# EVB-ANNA-B5_SCHEM_0001_Power.net
KiCad netlist of a schematic drawn in Altium Designer
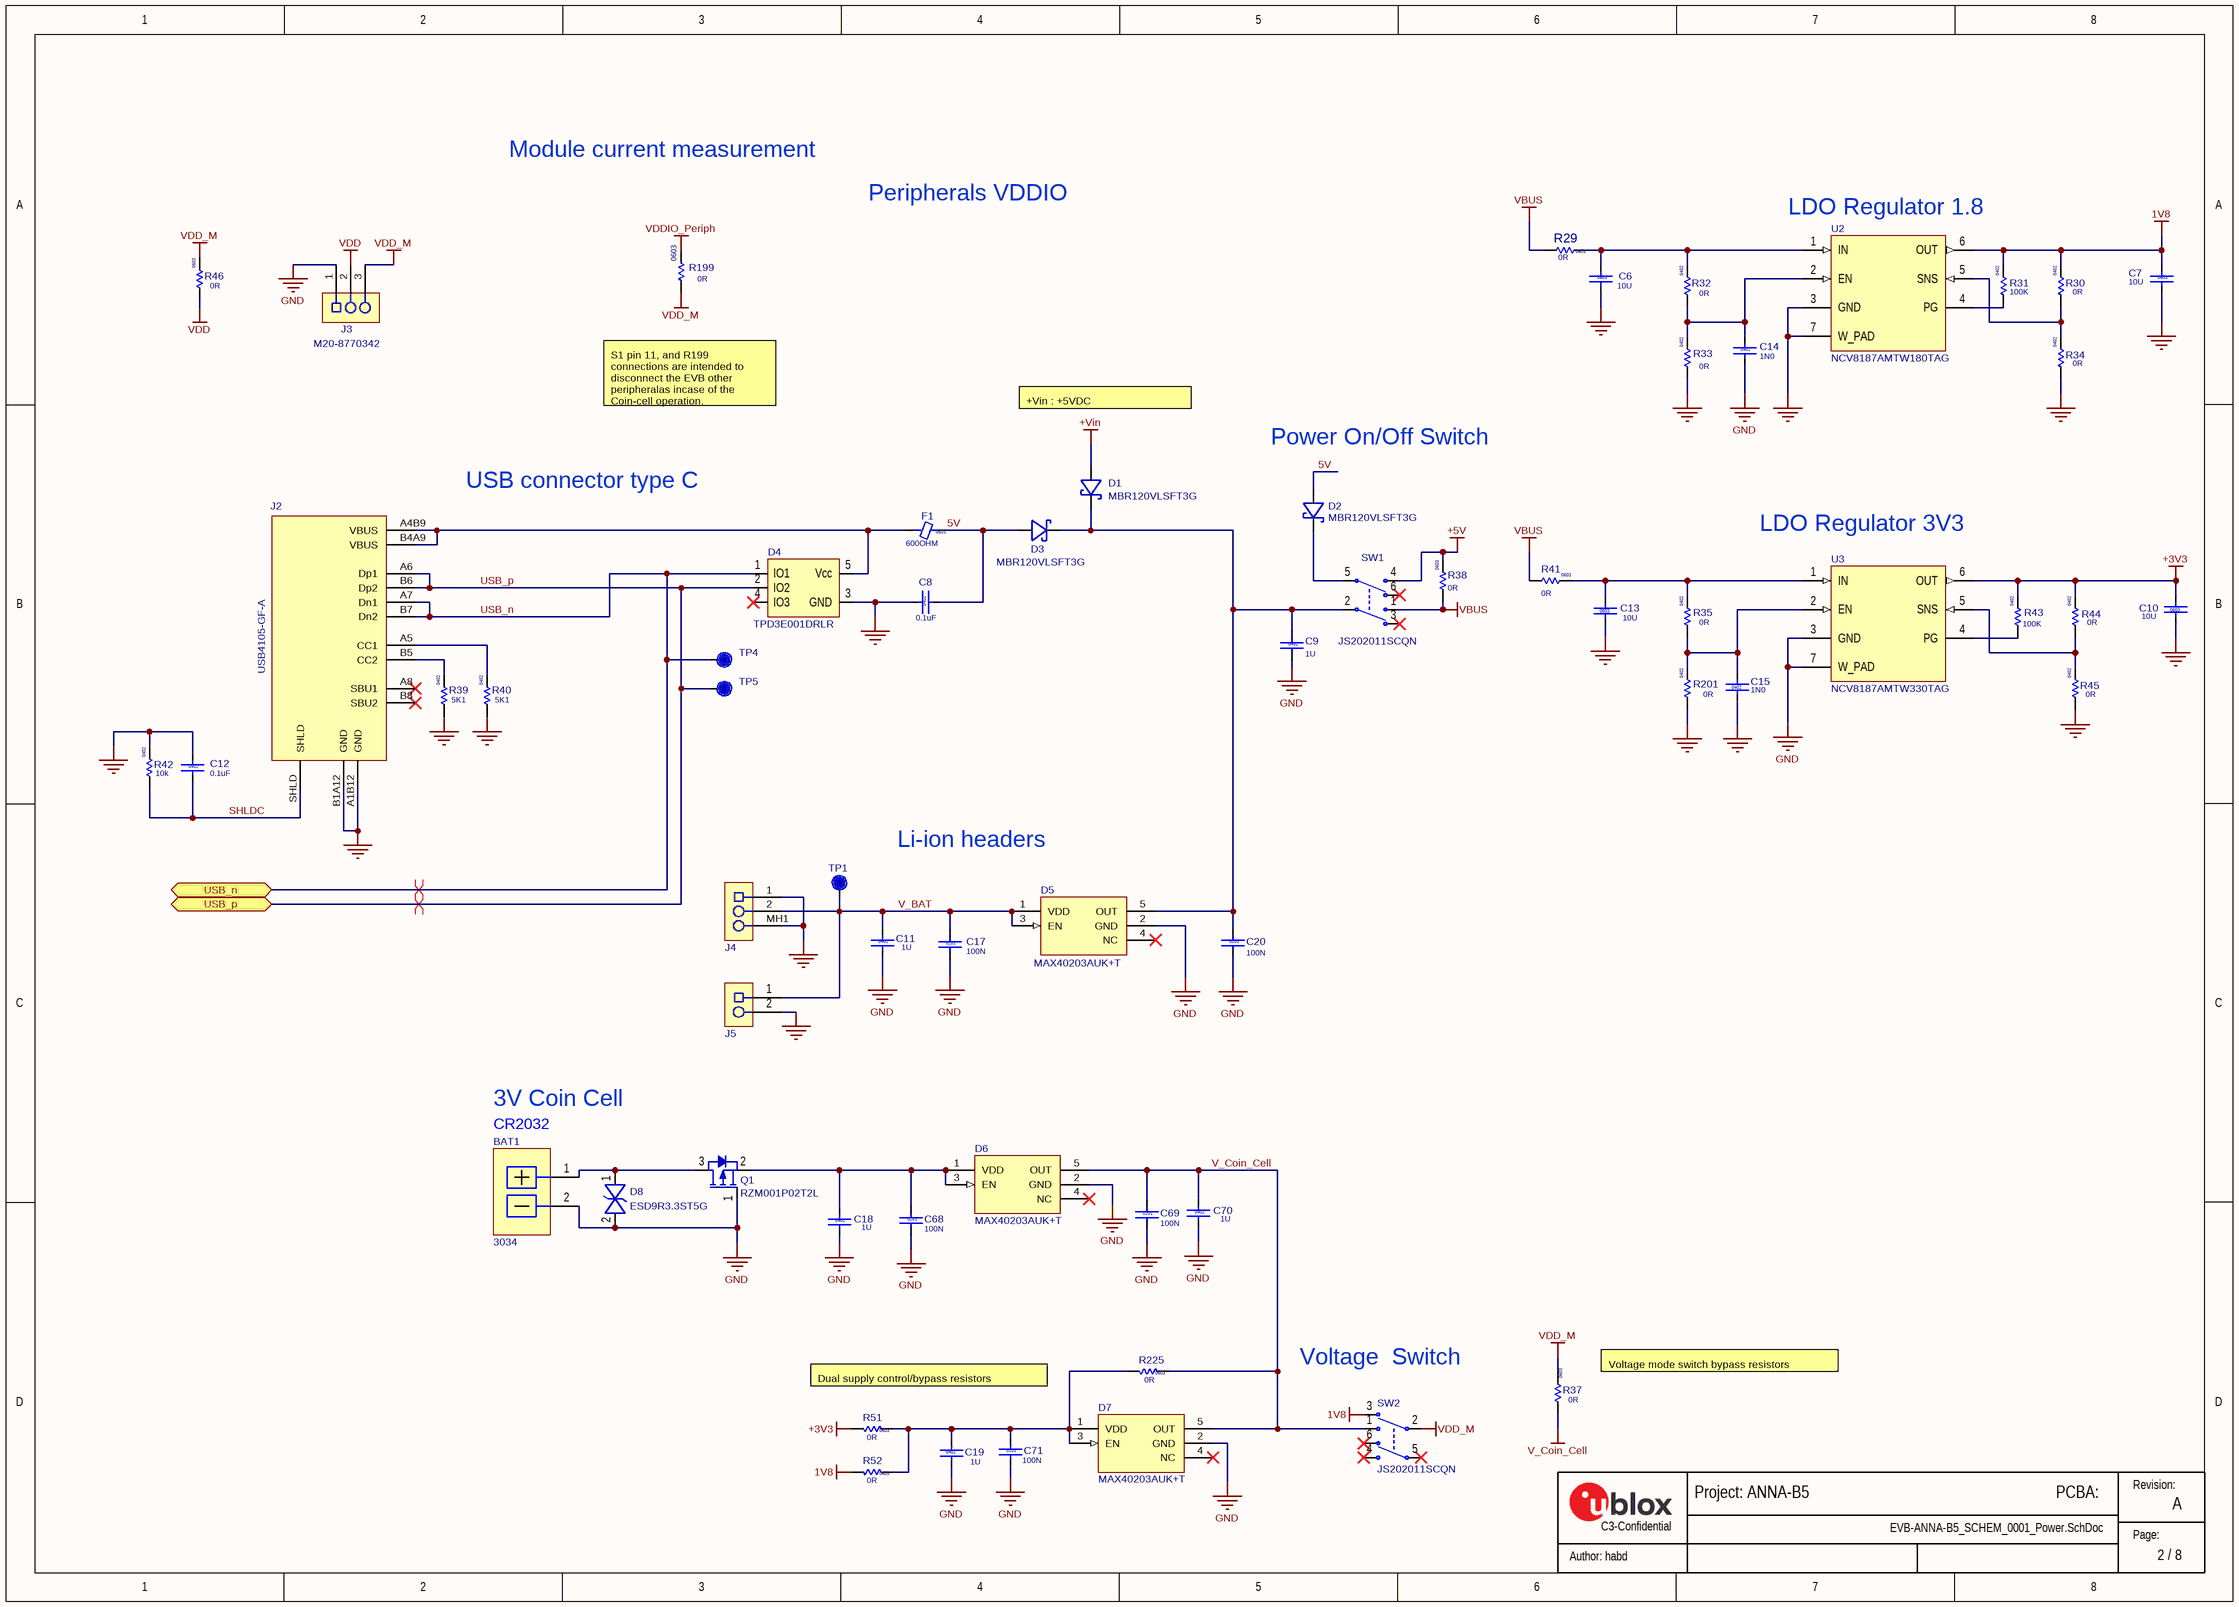
[diagram p0: EVB-ANNA-B5_SCHEM_0001_Power.SchDoc]

(export (version "E")
  (design (tool "Eeschema 10.0.6"))
  (components
    (comp (ref "BAT1")
      (value "UBXH03-0000009")
      (footprint "3034")
      (description "BATTERY HOLDER COIN SMT CR2020 CR2025 CR2032 KEYSTONE 3034")
      (fields
        (field (name "MANUFACTURER P/N") "3034")
        (field (name "MANUFACTURER") "Keystone Electronics Corporation")
        (field (name "EDITOR") "eric.moog")
      )
      (libsource (lib "UBX_Parts_DB_Lib") (part "Battery_2Pin"))
    )
    (comp (ref "C6")
      (value "10U")
      (footprint "CAP_0603_1750Lx950Wx850H_600x1000Pad_900G_FLX")
      (description "CAP CER X7R 0603 10U 20% 10V")
      (fields
        (field (name "SIZE") "0603")
        (field (name "PART NUMBER") "UBXH01-0000310")
        (field (name "TOLERANCE") "20%")
        (field (name "EDITOR") "michael.hein")
        (field (name "RELEASED BY") "martin.grasse")
      )
      (libsource (lib "UBX_Parts_DB_Lib") (part "Cap Chip"))
    )
    (comp (ref "C7")
      (value "10U")
      (footprint "CAP_0603_1750Lx950Wx850H_600x1000Pad_900G_FLX")
      (description "CAP CER X7R 0603 10U 20% 10V")
      (fields
        (field (name "SIZE") "0603")
        (field (name "PART NUMBER") "UBXH01-0000310")
        (field (name "TOLERANCE") "20%")
        (field (name "EDITOR") "michael.hein")
        (field (name "RELEASED BY") "martin.grasse")
      )
      (libsource (lib "UBX_Parts_DB_Lib") (part "Cap Chip"))
    )
    (comp (ref "C8")
      (value "0.1uF")
      (footprint "Cap 0402 HD")
      (description "Cap, Ceramic 0.1uF 10V 10% X5R 0402")
      (fields
        (field (name "SIZE") "0402")
        (field (name "PART NUMBER") "120-00016")
        (field (name "MANUFACTURER") "Murata Electronics North America")
      )
      (libsource (lib "Arena_Parts_DB_Lib") (part "Cap Chip"))
    )
    (comp (ref "C9")
      (value "1U")
      (footprint "Cap 0402 HD")
      (description "CAP CER X5R 0402 1U 10% 10V")
      (fields
        (field (name "SIZE") "0402")
        (field (name "PART NUMBER") "UBXH01-0000248")
        (field (name "TOLERANCE") "10%")
        (field (name "EDITOR") "michael.hein")
        (field (name "RELEASED BY") "igor.shevchenko")
      )
      (libsource (lib "UBX_Parts_DB_Lib") (part "Cap Chip"))
    )
    (comp (ref "C10")
      (value "10U")
      (footprint "CAP_0603_1750Lx950Wx850H_600x1000Pad_900G_FLX")
      (description "CAP CER X7R 0603 10U 20% 10V")
      (fields
        (field (name "SIZE") "0603")
        (field (name "PART NUMBER") "UBXH01-0000310")
        (field (name "TOLERANCE") "20%")
        (field (name "EDITOR") "michael.hein")
        (field (name "RELEASED BY") "martin.grasse")
      )
      (libsource (lib "UBX_Parts_DB_Lib") (part "Cap Chip"))
    )
    (comp (ref "C11")
      (value "1U")
      (footprint "Cap 0402 HD")
      (description "CAP CER X5R 0402 1U 10% 10V")
      (fields
        (field (name "SIZE") "0402")
        (field (name "PART NUMBER") "UBXH01-0000248")
        (field (name "TOLERANCE") "10%")
        (field (name "EDITOR") "michael.hein")
        (field (name "RELEASED BY") "igor.shevchenko")
      )
      (libsource (lib "UBX_Parts_DB_Lib") (part "Cap Chip"))
    )
    (comp (ref "C12")
      (value "0.1uF")
      (footprint "Cap 0402 HD")
      (description "Cap, Ceramic 0.1uF 10V 10% X5R 0402")
      (fields
        (field (name "SIZE") "0402")
        (field (name "PART NUMBER") "120-00016")
        (field (name "MANUFACTURER") "Murata Electronics North America")
      )
      (libsource (lib "Arena_Parts_DB_Lib") (part "Cap Chip"))
    )
    (comp (ref "C13")
      (value "10U")
      (footprint "CAP_0603_1750Lx950Wx850H_600x1000Pad_900G_FLX")
      (description "CAP CER X7R 0603 10U 20% 10V")
      (fields
        (field (name "SIZE") "0603")
        (field (name "PART NUMBER") "UBXH01-0000310")
        (field (name "TOLERANCE") "20%")
        (field (name "EDITOR") "michael.hein")
        (field (name "RELEASED BY") "martin.grasse")
      )
      (libsource (lib "UBX_Parts_DB_Lib") (part "Cap Chip"))
    )
    (comp (ref "C14")
      (value "1N0")
      (footprint "Cap 0402 HD")
      (description "CAP CER X7R 0402 1N0 10% 50V")
      (fields
        (field (name "SIZE") "0402")
        (field (name "PART NUMBER") "UBXH01-0000013")
        (field (name "TOLERANCE") "10%")
        (field (name "EDITOR") "massimo.vlacci")
        (field (name "RELEASED BY") "dario.antonaz")
      )
      (libsource (lib "UBX_Parts_DB_Lib") (part "Cap Chip"))
    )
    (comp (ref "C15")
      (value "1N0")
      (footprint "Cap 0402 HD")
      (description "CAP CER X7R 0402 1N0 10% 50V")
      (fields
        (field (name "SIZE") "0402")
        (field (name "PART NUMBER") "UBXH01-0000013")
        (field (name "TOLERANCE") "10%")
        (field (name "EDITOR") "massimo.vlacci")
        (field (name "RELEASED BY") "dario.antonaz")
      )
      (libsource (lib "UBX_Parts_DB_Lib") (part "Cap Chip"))
    )
    (comp (ref "C17")
      (value "100N")
      (footprint "Cap 0201 HD")
      (description "CAP CER X5R 0201 100N 10% 25V")
      (fields
        (field (name "CASE/PACKAGE") "0201")
        (field (name "TOLERANCE") "10%")
        (field (name "CRITICAL PART") "No")
        (field (name "OWNER") "Dario Antonaz (null)")
      )
      (libsource (lib "u-blox") (part "Cap Chip"))
    )
    (comp (ref "C18")
      (value "1U")
      (footprint "Cap 0402 HD")
      (description "CAP CER X5R 0402 1U 10% 10V")
      (fields
        (field (name "SIZE") "0402")
        (field (name "PART NUMBER") "UBXH01-0000248")
        (field (name "TOLERANCE") "10%")
        (field (name "EDITOR") "michael.hein")
        (field (name "RELEASED BY") "igor.shevchenko")
      )
      (libsource (lib "UBX_Parts_DB_Lib") (part "Cap Chip"))
    )
    (comp (ref "C19")
      (value "1U")
      (footprint "Cap 0402 HD")
      (description "CAP CER X5R 0402 1U 10% 10V")
      (fields
        (field (name "PART NUMBER") "UBXH01-0000248")
        (field (name "TOLERANCE") "10%")
        (field (name "SIZE") "0402")
        (field (name "EDITOR") "michael.hein")
        (field (name "RELEASED BY") "igor.shevchenko")
      )
      (libsource (lib "UBX_Parts_DB_Lib") (part "Cap Chip"))
    )
    (comp (ref "C20")
      (value "100N")
      (footprint "Cap 0201 HD")
      (description "CAP CER X5R 0201 100N 10% 25V")
      (fields
        (field (name "CASE/PACKAGE") "0201")
        (field (name "TOLERANCE") "10%")
        (field (name "CRITICAL PART") "No")
        (field (name "OWNER") "Dario Antonaz (null)")
      )
      (libsource (lib "u-blox") (part "Cap Chip"))
    )
    (comp (ref "C68")
      (value "100N")
      (footprint "Cap 0201 HD")
      (description "CAP CER X5R 0201 100N 10% 25V")
      (fields
        (field (name "CASE/PACKAGE") "0201")
        (field (name "TOLERANCE") "10%")
        (field (name "CRITICAL PART") "No")
        (field (name "OWNER") "Dario Antonaz (null)")
      )
      (libsource (lib "u-blox") (part "Cap Chip"))
    )
    (comp (ref "C69")
      (value "100N")
      (footprint "Cap 0201 HD")
      (description "CAP CER X5R 0201 100N 10% 25V")
      (fields
        (field (name "CASE/PACKAGE") "0201")
        (field (name "TOLERANCE") "10%")
        (field (name "CRITICAL PART") "No")
        (field (name "OWNER") "Dario Antonaz (null)")
      )
      (libsource (lib "u-blox") (part "Cap Chip"))
    )
    (comp (ref "C70")
      (value "1U")
      (footprint "Cap 0402 HD")
      (description "CAP CER X5R 0402 1U 10% 10V")
      (fields
        (field (name "SIZE") "0402")
        (field (name "PART NUMBER") "UBXH01-0000248")
        (field (name "TOLERANCE") "10%")
        (field (name "EDITOR") "michael.hein")
        (field (name "RELEASED BY") "igor.shevchenko")
      )
      (libsource (lib "UBX_Parts_DB_Lib") (part "Cap Chip"))
    )
    (comp (ref "C71")
      (value "100N")
      (footprint "Cap 0201 HD")
      (description "CAP CER X5R 0201 100N 10% 25V")
      (fields
        (field (name "CASE/PACKAGE") "0201")
        (field (name "TOLERANCE") "10%")
        (field (name "CRITICAL PART") "No")
        (field (name "OWNER") "Dario Antonaz (null)")
      )
      (libsource (lib "u-blox") (part "Cap Chip"))
    )
    (comp (ref "D1")
      (value "110-00005")
      (footprint "SOD-123F_U")
      (description "Diode, Schottky, 20V 1A SOD-123F, 340mV Vf @ 1A\nMBR120VLSFT3G")
      (fields (field (name "MANUFACTURER PART NUMBER 1") "MBR120VLSFT3G") (field (name "VOLTAGE") "20V"))
      (libsource (lib "Arena_Parts_DB_Lib") (part "Diode_Schottky"))
    )
    (comp (ref "D2")
      (value "110-00005")
      (footprint "SOD-123F_U")
      (description "Diode, Schottky, 20V 1A SOD-123F, 340mV Vf @ 1A\nMBR120VLSFT3G")
      (fields (field (name "MANUFACTURER PART NUMBER 1") "MBR120VLSFT3G") (field (name "VOLTAGE") "20V"))
      (libsource (lib "Arena_Parts_DB_Lib") (part "Diode_Schottky"))
    )
    (comp (ref "D3")
      (value "110-00005")
      (footprint "SOD-123F_U")
      (description "Diode, Schottky, 20V 1A SOD-123F, 340mV Vf @ 1A\nMBR120VLSFT3G")
      (fields (field (name "MANUFACTURER PART NUMBER 1") "MBR120VLSFT3G") (field (name "VOLTAGE") "20V"))
      (libsource (lib "Arena_Parts_DB_Lib") (part "Diode_Schottky"))
    )
    (comp (ref "D4")
      (value "110-00018")
      (footprint "SOT-553")
      (description "LOW-CAPACITANCE 3-CHANNEL ESD-PROTECTION ARRAY")
      (fields
        (field (name "MANUFACTURER P/N") "TPD3E001DRLR")
        (field (name "MANUFACTURER") "Texas Instruments")
        (field (name "VOLTAGE") "5V")
      )
      (libsource (lib "Arena_Parts_DB_Lib") (part "TPD3E001"))
    )
    (comp (ref "D5")
      (value "UBXH12-0000539")
      (footprint "SOT-23-5_2")
      (description "IDEAL DIODE OR CONTROLLER SOURCE SELECTOR SWITCH P-CHANNEL 1:1 SOT-23-5 5.5V 1A")
      (fields
        (field (name "VOLTAGE") "5.5V")
        (field (name "MANUFACTURER PART NUMBER 1") "MAX40203AUK+T")
        (field (name "MANUFACTURER") "Maxim")
        (field (name "EDITOR") "eric.moog")
      )
      (libsource (lib "UBX_Parts_DB_Lib") (part "MAX40203AUK"))
    )
    (comp (ref "D6")
      (value "UBXH12-0000539")
      (footprint "SOT-23-5_2")
      (description "IDEAL DIODE OR CONTROLLER SOURCE SELECTOR SWITCH P-CHANNEL 1:1 SOT-23-5 5.5V 1A")
      (fields
        (field (name "VOLTAGE") "5.5V")
        (field (name "MANUFACTURER PART NUMBER 1") "MAX40203AUK+T")
        (field (name "MANUFACTURER") "Maxim")
        (field (name "EDITOR") "eric.moog")
      )
      (libsource (lib "UBX_Parts_DB_Lib") (part "MAX40203AUK"))
    )
    (comp (ref "D7")
      (value "UBXH12-0000539")
      (footprint "SOT-23-5_2")
      (description "IDEAL DIODE OR CONTROLLER SOURCE SELECTOR SWITCH P-CHANNEL 1:1 SOT-23-5 5.5V 1A")
      (fields
        (field (name "VOLTAGE") "5.5V")
        (field (name "MANUFACTURER PART NUMBER 1") "MAX40203AUK+T")
        (field (name "MANUFACTURER") "Maxim")
        (field (name "EDITOR") "eric.moog")
      )
      (libsource (lib "UBX_Parts_DB_Lib") (part "MAX40203AUK"))
    )
    (comp (ref "D8")
      (value "UBXH07-0000034")
      (footprint "SOD-923")
      (description "ESD PROTECTION DIODE ULTRA LOW LEAKAGE SOD923 ON SEMI 3V3")
      (fields
        (field (name "MANUFACTURER") "ON Semiconductor")
        (field (name "MANUFACTURER P/N") "ESD9R3.3ST5G")
        (field (name "EDITOR") "pierpaolo.arban")
        (field (name "RELEASED BY") "dario.antonaz")
      )
      (libsource (lib "UBX_Parts_DB_Lib") (part "Diode_TVS"))
    )
    (comp (ref "F1")
      (value "600OHM")
      (footprint "IND_0603_1750Lx950Wx1050H_600x800Pad_800G_FLX")
      (description "FERRITE BEAD 0603 600 OHM AT 100MHZ 600OHM 500mA")
      (fields
        (field (name "SIZE") "0603")
        (field (name "PART NUMBER") "UBXH08-0000001")
        (field (name "MANUFACTURER") "TDK Corporation")
        (field (name "EDITOR") "daniel.hurni")
        (field (name "RELEASED BY") "martin.frauchiger")
      )
      (libsource (lib "UBX_Parts_DB_Lib") (part "FB sm"))
    )
    (comp (ref "J2")
      (value "USB4105-GF-A")
      (footprint "USB4105-GF-A")
      (description "CONN RCP USB2.0 TYP C 24P SMD RA 20V 6.25A")
      (fields
        (field (name "PART NUMBER") "UBXH04-0000785")
        (field (name "VOLTAGE") "<20V DC")
        (field (name "EDITOR") "eric.moog")
      )
      (libsource (lib "UBX_Parts_DB_Lib") (part "USB4105-GF-A"))
    )
    (comp (ref "J3")
      (value "UBXH04-0000792")
      (footprint "HDR-0.1P-3Pin-1Row-SMT")
      (description "1-ROW SMD CONN 100MIL GRID 3 -PIN 100V 3A")
      (fields
        (field (name "MANUFACTURER P/N") "M20-8770342")
        (field (name "MANUFACTURER") "HARWiN")
        (field (name "EDITOR") "eric.moog")
      )
      (libsource (lib "UBX_Parts_DB_Lib") (part "CON-3Pin_1Row"))
    )
    (comp (ref "J4")
      (value "UBXH04-0000791")
      (footprint "B2B-PH-SM4-TB")
      (description "CONN 1-ROW SMT 2.0MM GRID 2-PIN VERT 100V 2A")
      (fields
        (field (name "VOLTAGE") "None")
        (field (name "MANUFACTURER") "JST")
        (field (name "EDITOR") "eric.moog")
      )
      (libsource (lib "UBX_Parts_DB_Lib") (part "CON-2Pin_1Row_W-MH"))
    )
    (comp (ref "J5")
      (value "UBXH04-0000026")
      (footprint "HDR-0.1P-2PIN-TH")
      (description "1-ROW TH-PCB SOCKETS 100MIL GRID 2-PIN 0.64MM SQUARE POLARIZE")
      (fields
        (field (name "MANUFACTURER") "HARWiN")
        (field (name "EDITOR") "roland.rust")
        (field (name "RELEASED BY") "alvaro.nussbaum")
      )
      (libsource (lib "UBX_Parts_DB_Lib") (part "CON-2Pin_1Row"))
    )
    (comp (ref "Q1")
      (value "140-00005")
      (footprint "SOT-723")
      (description "P-MOSFET, 20V, 100mA, SOT-723-3")
      (fields (field (name "VOLTAGE") "20V") (field (name "MANUFACTURER PART NUMBER 1") "RZM001P02T2L"))
      (libsource (lib "Arena_Parts_DB_Lib") (part "MOSFET-P"))
    )
    (comp (ref "R29")
      (value "0R")
      (footprint "RES_0603_1700Lx950Wx600H_600x1000Pad_800G_FLX")
      (description "RES THICK FILM CHIP 0603 0R 0 100mW")
      (fields
        (field (name "SIZE") "0603")
        (field (name "PART NUMBER") "UBXH18-0003001")
        (field (name "TOLERANCE") "0")
        (field (name "EDITOR") "martin.frauchiger")
        (field (name "RELEASED BY") "martin.frauchiger")
      )
      (libsource (lib "UBX_Parts_DB_Lib") (part "Res sm"))
    )
    (comp (ref "R30")
      (value "0R")
      (footprint "RES 0402 HD")
      (description "RES THICK FILM CHIP 0402 0R 0 100mW")
      (fields
        (field (name "SIZE") "0402")
        (field (name "PART NUMBER") "UBXH18-0003002")
        (field (name "TOLERANCE") "0")
        (field (name "EDITOR") "charlotte.biber")
        (field (name "RELEASED BY") "peter.mueller")
      )
      (libsource (lib "UBX_Parts_DB_Lib") (part "Res sm"))
    )
    (comp (ref "R31")
      (value "100K")
      (footprint "RES 0402 HD")
      (description "RES THICK FILM CHIP 0402 100K 1% 63mW")
      (fields
        (field (name "SIZE") "0402")
        (field (name "PART NUMBER") "UBXH18-0000005")
        (field (name "TOLERANCE") "1%")
        (field (name "EDITOR") "dario.antonaz")
        (field (name "RELEASED BY") "sandro.sestan")
      )
      (libsource (lib "UBX_Parts_DB_Lib") (part "Res sm"))
    )
    (comp (ref "R32")
      (value "0R")
      (footprint "RES 0402 HD")
      (description "RES THICK FILM CHIP 0402 0R 0 100mW")
      (fields
        (field (name "SIZE") "0402")
        (field (name "PART NUMBER") "UBXH18-0003002")
        (field (name "TOLERANCE") "0")
        (field (name "EDITOR") "charlotte.biber")
        (field (name "RELEASED BY") "peter.mueller")
      )
      (libsource (lib "UBX_Parts_DB_Lib") (part "Res sm"))
    )
    (comp (ref "R33")
      (value "0R")
      (footprint "RES 0402 HD")
      (description "RES THICK FILM CHIP 0402 0R 0 100mW")
      (fields
        (field (name "SIZE") "0402")
        (field (name "PART NUMBER") "UBXH18-0003002")
        (field (name "TOLERANCE") "0")
        (field (name "EDITOR") "charlotte.biber")
        (field (name "RELEASED BY") "peter.mueller")
      )
      (libsource (lib "UBX_Parts_DB_Lib") (part "Res sm"))
    )
    (comp (ref "R34")
      (value "0R")
      (footprint "RES 0402 HD")
      (description "RES THICK FILM CHIP 0402 0R 0 100mW")
      (fields
        (field (name "SIZE") "0402")
        (field (name "PART NUMBER") "UBXH18-0003002")
        (field (name "TOLERANCE") "0")
        (field (name "EDITOR") "charlotte.biber")
        (field (name "RELEASED BY") "peter.mueller")
      )
      (libsource (lib "UBX_Parts_DB_Lib") (part "Res sm"))
    )
    (comp (ref "R35")
      (value "0R")
      (footprint "RES 0402 HD")
      (description "RES THICK FILM CHIP 0402 0R 0 100mW")
      (fields
        (field (name "SIZE") "0402")
        (field (name "PART NUMBER") "UBXH18-0003002")
        (field (name "TOLERANCE") "0")
        (field (name "EDITOR") "charlotte.biber")
        (field (name "RELEASED BY") "peter.mueller")
      )
      (libsource (lib "UBX_Parts_DB_Lib") (part "Res sm"))
    )
    (comp (ref "R37")
      (value "0R")
      (footprint "RES_0603_1700Lx950Wx600H_600x1000Pad_800G_FLX")
      (description "RES THICK FILM CHIP 0603 0R 0 100mW")
      (fields
        (field (name "SIZE") "0603")
        (field (name "PART NUMBER") "UBXH18-0003001")
        (field (name "TOLERANCE") "0")
        (field (name "EDITOR") "martin.frauchiger")
        (field (name "RELEASED BY") "martin.frauchiger")
      )
      (libsource (lib "UBX_Parts_DB_Lib") (part "Res sm"))
    )
    (comp (ref "R38")
      (value "0R")
      (footprint "RES_0603_1700Lx950Wx600H_600x1000Pad_800G_FLX")
      (description "RES THICK FILM CHIP 0603 0R 0 100mW")
      (fields
        (field (name "SIZE") "0603")
        (field (name "PART NUMBER") "UBXH18-0003001")
        (field (name "TOLERANCE") "0")
        (field (name "EDITOR") "martin.frauchiger")
        (field (name "RELEASED BY") "martin.frauchiger")
      )
      (libsource (lib "UBX_Parts_DB_Lib") (part "Res sm"))
    )
    (comp (ref "R39")
      (value "5K1")
      (footprint "RES 0402 HD")
      (description "RES THICK FILM CHIP 0402 5K1 5% 100mW")
      (fields
        (field (name "SIZE") "0402")
        (field (name "PART NUMBER") "UBXH18-0008066")
        (field (name "TOLERANCE") "5%")
        (field (name "EDITOR") "alvaro.nussbaum")
        (field (name "RELEASED BY") "roland.rust")
      )
      (libsource (lib "UBX_Parts_DB_Lib") (part "Res sm"))
    )
    (comp (ref "R40")
      (value "5K1")
      (footprint "RES 0402 HD")
      (description "RES THICK FILM CHIP 0402 5K1 5% 100mW")
      (fields
        (field (name "SIZE") "0402")
        (field (name "PART NUMBER") "UBXH18-0008066")
        (field (name "TOLERANCE") "5%")
        (field (name "EDITOR") "alvaro.nussbaum")
        (field (name "RELEASED BY") "roland.rust")
      )
      (libsource (lib "UBX_Parts_DB_Lib") (part "Res sm"))
    )
    (comp (ref "R41")
      (value "0R")
      (footprint "RES_0603_1700Lx950Wx600H_600x1000Pad_800G_FLX")
      (description "RES THICK FILM CHIP 0603 0R 0 100mW")
      (fields
        (field (name "SIZE") "0603")
        (field (name "PART NUMBER") "UBXH18-0003001")
        (field (name "TOLERANCE") "0")
        (field (name "EDITOR") "martin.frauchiger")
        (field (name "RELEASED BY") "martin.frauchiger")
      )
      (libsource (lib "UBX_Parts_DB_Lib") (part "Res sm"))
    )
    (comp (ref "R42")
      (value "10k")
      (footprint "RES 0402 HD")
      (description "Resistor 10k ohm 1% 1/16W, 0402")
      (fields
        (field (name "SIZE") "0402")
        (field (name "PART NUMBER") "180-00024")
        (field (name "POWER") "1/16W")
      )
      (libsource (lib "Arena_Parts_DB_Lib") (part "Res sm"))
    )
    (comp (ref "R43")
      (value "100K")
      (footprint "RES 0402 HD")
      (description "RES THICK FILM CHIP 0402 100K 1% 63mW")
      (fields
        (field (name "SIZE") "0402")
        (field (name "PART NUMBER") "UBXH18-0000005")
        (field (name "TOLERANCE") "1%")
        (field (name "EDITOR") "dario.antonaz")
        (field (name "RELEASED BY") "sandro.sestan")
      )
      (libsource (lib "UBX_Parts_DB_Lib") (part "Res sm"))
    )
    (comp (ref "R44")
      (value "0R")
      (footprint "RES 0402 HD")
      (description "RES THICK FILM CHIP 0402 0R 0 100mW")
      (fields
        (field (name "SIZE") "0402")
        (field (name "PART NUMBER") "UBXH18-0003002")
        (field (name "TOLERANCE") "0")
        (field (name "EDITOR") "charlotte.biber")
        (field (name "RELEASED BY") "peter.mueller")
      )
      (libsource (lib "UBX_Parts_DB_Lib") (part "Res sm"))
    )
    (comp (ref "R45")
      (value "0R")
      (footprint "RES 0402 HD")
      (description "RES THICK FILM CHIP 0402 0R 0 100mW")
      (fields
        (field (name "SIZE") "0402")
        (field (name "PART NUMBER") "UBXH18-0003002")
        (field (name "TOLERANCE") "0")
        (field (name "EDITOR") "charlotte.biber")
        (field (name "RELEASED BY") "peter.mueller")
      )
      (libsource (lib "UBX_Parts_DB_Lib") (part "Res sm"))
    )
    (comp (ref "R46")
      (value "0R")
      (footprint "RES_0603_1700Lx950Wx600H_600x1000Pad_800G_FLX")
      (description "RES THICK FILM CHIP 0603 0R 0 100mW")
      (fields
        (field (name "SIZE") "0603")
        (field (name "PART NUMBER") "UBXH18-0003001")
        (field (name "TOLERANCE") "0")
        (field (name "EDITOR") "martin.frauchiger")
        (field (name "RELEASED BY") "martin.frauchiger")
      )
      (libsource (lib "UBX_Parts_DB_Lib") (part "Res sm"))
    )
    (comp (ref "R51")
      (value "0R")
      (footprint "RES_0603_1700Lx950Wx600H_600x1000Pad_800G_FLX")
      (description "RES THICK FILM CHIP 0603 0R 0 100mW")
      (fields
        (field (name "SIZE") "0603")
        (field (name "PART NUMBER") "UBXH18-0003001")
        (field (name "TOLERANCE") "0")
        (field (name "EDITOR") "martin.frauchiger")
        (field (name "RELEASED BY") "martin.frauchiger")
      )
      (libsource (lib "UBX_Parts_DB_Lib") (part "Res sm"))
    )
    (comp (ref "R52")
      (value "0R")
      (footprint "RES_0603_1700Lx950Wx600H_600x1000Pad_800G_FLX")
      (description "RES THICK FILM CHIP 0603 0R 0 100mW")
      (fields
        (field (name "SIZE") "0603")
        (field (name "PART NUMBER") "UBXH18-0003001")
        (field (name "TOLERANCE") "0")
        (field (name "EDITOR") "martin.frauchiger")
        (field (name "RELEASED BY") "martin.frauchiger")
      )
      (libsource (lib "UBX_Parts_DB_Lib") (part "Res sm"))
    )
    (comp (ref "R199")
      (value "0R")
      (footprint "RES_0603_1700Lx950Wx600H_600x1000Pad_800G_FLX")
      (description "RES THICK FILM CHIP 0603 0R 0 100mW")
      (fields
        (field (name "SIZE") "0603")
        (field (name "PART NUMBER") "UBXH18-0003001")
        (field (name "TOLERANCE") "0")
        (field (name "EDITOR") "martin.frauchiger")
        (field (name "RELEASED BY") "martin.frauchiger")
      )
      (libsource (lib "UBX_Parts_DB_Lib") (part "Res sm"))
    )
    (comp (ref "R201")
      (value "0R")
      (footprint "RES 0402 HD")
      (description "RES THICK FILM CHIP 0402 0R 0 100mW")
      (fields
        (field (name "SIZE") "0402")
        (field (name "PART NUMBER") "UBXH18-0003002")
        (field (name "TOLERANCE") "0")
        (field (name "EDITOR") "charlotte.biber")
        (field (name "RELEASED BY") "peter.mueller")
      )
      (libsource (lib "UBX_Parts_DB_Lib") (part "Res sm"))
    )
    (comp (ref "R225")
      (value "0R")
      (footprint "RES_0603_1700Lx950Wx600H_600x1000Pad_800G_FLX")
      (description "RES THICK FILM CHIP 0603 0R 0 100mW")
      (fields
        (field (name "SIZE") "0603")
        (field (name "PART NUMBER") "UBXH18-0003001")
        (field (name "TOLERANCE") "0")
        (field (name "EDITOR") "martin.frauchiger")
        (field (name "RELEASED BY") "martin.frauchiger")
      )
      (libsource (lib "UBX_Parts_DB_Lib") (part "Res sm"))
    )
    (comp (ref "SW1")
      (value "UBXH19-0000050")
      (footprint "SW_Slide_DPDT_JS202011SCQN")
      (description "2 WAY ON-ON SUB-MINIATURE SLIDE SWITCH SMD JS SERIES")
      (fields
        (field (name "MANUFACTURER P/N") "JS202011SCQN")
        (field (name "MANUFACTURER") "C&K Components")
        (field (name "EDITOR") "andre.pick")
        (field (name "RELEASED BY") "martin.pilik")
      )
      (libsource (lib "UBX_Parts_DB_Lib") (part "SW_DPDT_JS2020"))
    )
    (comp (ref "SW2")
      (value "UBXH19-0000050")
      (footprint "SW_Slide_DPDT_JS202011SCQN")
      (description "2 WAY ON-ON SUB-MINIATURE SLIDE SWITCH SMD JS SERIES")
      (fields
        (field (name "MANUFACTURER P/N") "JS202011SCQN")
        (field (name "MANUFACTURER") "C&K Components")
        (field (name "EDITOR") "andre.pick")
        (field (name "RELEASED BY") "martin.pilik")
      )
      (libsource (lib "UBX_Parts_DB_Lib") (part "SW_DPDT_JS2020"))
    )
    (comp (ref "TP1")
      (value "TP10R")
      (footprint "TP10R")
      (description "Testpoint, Round 1.0mm Dia")
      (fields (field (name "ADDED BY") "Jeremy D") (field (name "CHECKED BY") "Paul B"))
      (libsource (lib "LEGACY_Rigado_AltiumLib") (part "TP_R"))
    )
    (comp (ref "TP4")
      (value "TP10R")
      (footprint "TP10R")
      (description "Testpoint, Round 1.0mm Dia")
      (fields (field (name "ADDED BY") "Jeremy D") (field (name "CHECKED BY") "Paul B"))
      (libsource (lib "") (part "TP_R_1"))
    )
    (comp (ref "TP5")
      (value "TP10R")
      (footprint "TP10R")
      (description "Testpoint, Round 1.0mm Dia")
      (fields (field (name "ADDED BY") "Jeremy D") (field (name "CHECKED BY") "Paul B"))
      (libsource (lib "") (part "TP_R_1"))
    )
    (comp (ref "U2")
      (value "UBXH43-0000004")
      (footprint "DFN0.65P-6Pin_W-Pad")
      (description "LDO REGULATOR 1.8V,LOW Iq, WDFNW6 2x2 MM PACKAGE 1200 mA")
      (fields
        (field (name "MANUFACTURER PART NUMBER 1") "NCV8187AMTW180TAG")
        (field (name "OWNER") "Hozaifa Abdelgadir")
      )
      (libsource (lib "UBX_Arena") (part "NCV8187"))
    )
    (comp (ref "U3")
      (value "UBXH43-0000003")
      (footprint "DFN0.65P-6Pin_W-Pad")
      (description "LDO REGULATOR 3.3V,LOW Iq, WDFNW6 2x2 MM, 0.65P PACKAGE 1200 mA")
      (fields
        (field (name "MANUFACTURER PART NUMBER 1") "NCV8187AMTW330TAG")
        (field (name "OWNER") "Hozaifa Abdelgadir")
      )
      (libsource (lib "UBX_Arena") (part "NCV8187"))
    )
  )
  (nets
    (net (code "1") (name "+3V3") (class "Default")
      (node (ref "C10") (pin "1") (pinfunction "1_1") (pintype "passive"))
      (node (ref "R43") (pin "2") (pinfunction "2_2") (pintype "passive"))
      (node (ref "R44") (pin "2") (pinfunction "2_2") (pintype "passive"))
      (node (ref "R51") (pin "2") (pinfunction "2_2") (pintype "passive"))
      (node (ref "U3") (pin "6") (pinfunction "OUT_6") (pintype "output"))
    )
    (net (code "2") (name "+5V") (class "Default")
      (node (ref "R38") (pin "2") (pinfunction "2_2") (pintype "passive"))
      (node (ref "SW1") (pin "4") (pinfunction "N.O-2_4") (pintype "passive"))
    )
    (net (code "3") (name "+Vin") (class "Default")
      (node (ref "D1") (pin "A") (pinfunction "Anode_A") (pintype "passive"))
    )
    (net (code "4") (name "/5V") (class "Default")
      (node (ref "C8") (pin "2") (pinfunction "2_2") (pintype "passive"))
      (node (ref "D2") (pin "A") (pinfunction "Anode_A") (pintype "passive"))
      (node (ref "D3") (pin "A") (pinfunction "Anode_A") (pintype "passive"))
      (node (ref "F1") (pin "2") (pinfunction "2_2") (pintype "passive"))
    )
    (net (code "5") (name "/SHLDC") (class "Default")
      (node (ref "C12") (pin "2") (pinfunction "2_2") (pintype "passive"))
      (node (ref "J2") (pin "SHLD") (pinfunction "SHLD_SHLD") (pintype "power_in"))
      (node (ref "R42") (pin "1") (pinfunction "1_1") (pintype "passive"))
    )
    (net (code "6") (name "/USB_n") (class "Default")
      (node (ref "D4") (pin "1") (pinfunction "IO1_1") (pintype "passive"))
      (node (ref "J2") (pin "A7") (pinfunction "Dn1_A7") (pintype "power_in"))
      (node (ref "J2") (pin "B7") (pinfunction "Dn2_B7") (pintype "power_in"))
      (node (ref "TP4") (pin "1") (pintype "passive"))
    )
    (net (code "7") (name "/USB_p") (class "Default")
      (node (ref "D4") (pin "2") (pinfunction "IO2_2") (pintype "passive"))
      (node (ref "J2") (pin "A6") (pinfunction "Dp1_A6") (pintype "power_in"))
      (node (ref "J2") (pin "B6") (pinfunction "Dp2_B6") (pintype "power_in"))
      (node (ref "TP5") (pin "1") (pintype "passive"))
    )
    (net (code "8") (name "/V_BAT") (class "Default")
      (node (ref "C11") (pin "1") (pinfunction "1_1") (pintype "passive"))
      (node (ref "C17") (pin "1") (pinfunction "1_1") (pintype "passive"))
      (node (ref "D5") (pin "1") (pinfunction "VDD_1") (pintype "power_in"))
      (node (ref "D5") (pin "3") (pinfunction "EN_3") (pintype "input"))
      (node (ref "J4") (pin "2") (pinfunction "2_2") (pintype "passive"))
      (node (ref "J5") (pin "1") (pinfunction "1_1") (pintype "passive"))
      (node (ref "TP1") (pin "1") (pintype "passive"))
    )
    (net (code "9") (name "1V8") (class "Default")
      (node (ref "C7") (pin "1") (pinfunction "1_1") (pintype "passive"))
      (node (ref "R30") (pin "2") (pinfunction "2_2") (pintype "passive"))
      (node (ref "R31") (pin "2") (pinfunction "2_2") (pintype "passive"))
      (node (ref "R52") (pin "2") (pinfunction "2_2") (pintype "passive"))
      (node (ref "SW2") (pin "3") (pinfunction "N.C-1_3") (pintype "passive"))
      (node (ref "U2") (pin "6") (pinfunction "OUT_6") (pintype "output"))
    )
    (net (code "10") (name "GND") (class "Default")
      (node (ref "BAT1") (pin "2") (pinfunction "2_2") (pintype "power_in"))
      (node (ref "C10") (pin "2") (pinfunction "2_2") (pintype "passive"))
      (node (ref "C11") (pin "2") (pinfunction "2_2") (pintype "passive"))
      (node (ref "C12") (pin "1") (pinfunction "1_1") (pintype "passive"))
      (node (ref "C13") (pin "2") (pinfunction "2_2") (pintype "passive"))
      (node (ref "C14") (pin "2") (pinfunction "2_2") (pintype "passive"))
      (node (ref "C15") (pin "1") (pinfunction "1_1") (pintype "passive"))
      (node (ref "C17") (pin "2") (pinfunction "2_2") (pintype "passive"))
      (node (ref "C18") (pin "2") (pinfunction "2_2") (pintype "passive"))
      (node (ref "C19") (pin "2") (pinfunction "2_2") (pintype "passive"))
      (node (ref "C20") (pin "2") (pinfunction "2_2") (pintype "passive"))
      (node (ref "C6") (pin "2") (pinfunction "2_2") (pintype "passive"))
      (node (ref "C68") (pin "2") (pinfunction "2_2") (pintype "passive"))
      (node (ref "C69") (pin "2") (pinfunction "2_2") (pintype "passive"))
      (node (ref "C7") (pin "2") (pinfunction "2_2") (pintype "passive"))
      (node (ref "C70") (pin "2") (pinfunction "2_2") (pintype "passive"))
      (node (ref "C71") (pin "2") (pinfunction "2_2") (pintype "passive"))
      (node (ref "C8") (pin "1") (pinfunction "1_1") (pintype "passive"))
      (node (ref "C9") (pin "2") (pinfunction "2_2") (pintype "passive"))
      (node (ref "D4") (pin "3") (pinfunction "GND_3") (pintype "power_in"))
      (node (ref "D5") (pin "2") (pinfunction "GND_2") (pintype "power_in"))
      (node (ref "D6") (pin "2") (pinfunction "GND_2") (pintype "power_in"))
      (node (ref "D7") (pin "2") (pinfunction "GND_2") (pintype "power_in"))
      (node (ref "D8") (pin "2") (pintype "passive"))
      (node (ref "J2") (pin "A1B12") (pinfunction "GND_A1B12") (pintype "power_in"))
      (node (ref "J2") (pin "B1A12") (pinfunction "GND_B1A12") (pintype "power_in"))
      (node (ref "J3") (pin "1") (pinfunction "1_1") (pintype "passive"))
      (node (ref "J4") (pin "1") (pinfunction "1_1") (pintype "passive"))
      (node (ref "J4") (pin "MH1") (pinfunction "MH1_MH1") (pintype "passive"))
      (node (ref "J5") (pin "2") (pinfunction "2_2") (pintype "passive"))
      (node (ref "Q1") (pin "1") (pinfunction "G_1") (pintype "passive"))
      (node (ref "R201") (pin "1") (pinfunction "1_1") (pintype "passive"))
      (node (ref "R33") (pin "1") (pinfunction "1_1") (pintype "passive"))
      (node (ref "R34") (pin "1") (pinfunction "1_1") (pintype "passive"))
      (node (ref "R39") (pin "1") (pinfunction "1_1") (pintype "passive"))
      (node (ref "R40") (pin "1") (pinfunction "1_1") (pintype "passive"))
      (node (ref "R42") (pin "2") (pinfunction "2_2") (pintype "passive"))
      (node (ref "R45") (pin "1") (pinfunction "1_1") (pintype "passive"))
      (node (ref "U2") (pin "3") (pinfunction "GND_3") (pintype "power_in"))
      (node (ref "U2") (pin "7") (pinfunction "W_PAD_7") (pintype "power_in"))
      (node (ref "U3") (pin "3") (pinfunction "GND_3") (pintype "power_in"))
      (node (ref "U3") (pin "7") (pinfunction "W_PAD_7") (pintype "power_in"))
    )
    (net (code "11") (name "Net-(D1-Cathode)") (class "Default")
      (node (ref "C20") (pin "1") (pinfunction "1_1") (pintype "passive"))
      (node (ref "C9") (pin "1") (pinfunction "1_1") (pintype "passive"))
      (node (ref "D1") (pin "C") (pinfunction "Cathode_C") (pintype "passive"))
      (node (ref "D3") (pin "C") (pinfunction "Cathode_C") (pintype "passive"))
      (node (ref "D5") (pin "5") (pinfunction "OUT_5") (pintype "power_in"))
      (node (ref "SW1") (pin "2") (pinfunction "COM-1_2") (pintype "passive"))
    )
    (net (code "12") (name "Net-(D2-Cathode)") (class "Default")
      (node (ref "D2") (pin "C") (pinfunction "Cathode_C") (pintype "passive"))
      (node (ref "SW1") (pin "5") (pinfunction "COM-2_5") (pintype "passive"))
    )
    (net (code "13") (name "Net-(D4-Vcc)") (class "Default")
      (node (ref "D4") (pin "5") (pinfunction "Vcc_5") (pintype "power_in"))
      (node (ref "F1") (pin "1") (pinfunction "1_1") (pintype "passive"))
      (node (ref "J2") (pin "A4B9") (pinfunction "VBUS_A4B9") (pintype "power_in"))
      (node (ref "J2") (pin "B4A9") (pinfunction "VBUS_B4A9") (pintype "power_in"))
    )
    (net (code "14") (name "Net-(D6-EN)") (class "Default")
      (node (ref "C18") (pin "1") (pinfunction "1_1") (pintype "passive"))
      (node (ref "C68") (pin "1") (pinfunction "1_1") (pintype "passive"))
      (node (ref "D6") (pin "1") (pinfunction "VDD_1") (pintype "power_in"))
      (node (ref "D6") (pin "3") (pinfunction "EN_3") (pintype "input"))
      (node (ref "Q1") (pin "2") (pinfunction "S_2") (pintype "passive"))
    )
    (net (code "15") (name "Net-(D7-EN)") (class "Default")
      (node (ref "C19") (pin "1") (pinfunction "1_1") (pintype "passive"))
      (node (ref "C71") (pin "1") (pinfunction "1_1") (pintype "passive"))
      (node (ref "D7") (pin "1") (pinfunction "VDD_1") (pintype "power_in"))
      (node (ref "D7") (pin "3") (pinfunction "EN_3") (pintype "input"))
      (node (ref "R225") (pin "2") (pinfunction "2_2") (pintype "passive"))
      (node (ref "R51") (pin "1") (pinfunction "1_1") (pintype "passive"))
      (node (ref "R52") (pin "1") (pinfunction "1_1") (pintype "passive"))
    )
    (net (code "16") (name "Net-(J2-CC1)") (class "Default")
      (node (ref "J2") (pin "A5") (pinfunction "CC1_A5") (pintype "power_in"))
      (node (ref "R40") (pin "2") (pinfunction "2_2") (pintype "passive"))
    )
    (net (code "17") (name "Net-(J2-CC2)") (class "Default")
      (node (ref "J2") (pin "B5") (pinfunction "CC2_B5") (pintype "power_in"))
      (node (ref "R39") (pin "2") (pinfunction "2_2") (pintype "passive"))
    )
    (net (code "18") (name "Net-(Q1-D)") (class "Default")
      (node (ref "BAT1") (pin "1") (pinfunction "1_1") (pintype "power_in"))
      (node (ref "D8") (pin "1") (pintype "passive"))
      (node (ref "Q1") (pin "3") (pinfunction "D_3") (pintype "passive"))
    )
    (net (code "19") (name "Net-(U2-EN)") (class "Default")
      (node (ref "C14") (pin "1") (pinfunction "1_1") (pintype "passive"))
      (node (ref "R32") (pin "1") (pinfunction "1_1") (pintype "passive"))
      (node (ref "R33") (pin "2") (pinfunction "2_2") (pintype "passive"))
      (node (ref "U2") (pin "2") (pinfunction "EN_2") (pintype "input"))
    )
    (net (code "20") (name "Net-(U2-IN)") (class "Default")
      (node (ref "C6") (pin "1") (pinfunction "1_1") (pintype "passive"))
      (node (ref "R29") (pin "2") (pinfunction "2_2") (pintype "passive"))
      (node (ref "R32") (pin "2") (pinfunction "2_2") (pintype "passive"))
      (node (ref "U2") (pin "1") (pinfunction "IN_1") (pintype "input"))
    )
    (net (code "21") (name "Net-(U2-PG)") (class "Default")
      (node (ref "R31") (pin "1") (pinfunction "1_1") (pintype "passive"))
      (node (ref "U2") (pin "4") (pinfunction "PG_4") (pintype "open_collector"))
    )
    (net (code "22") (name "Net-(U2-SNS)") (class "Default")
      (node (ref "R30") (pin "1") (pinfunction "1_1") (pintype "passive"))
      (node (ref "R34") (pin "2") (pinfunction "2_2") (pintype "passive"))
      (node (ref "U2") (pin "5") (pinfunction "SNS_5") (pintype "input"))
    )
    (net (code "23") (name "Net-(U3-EN)") (class "Default")
      (node (ref "C15") (pin "2") (pinfunction "2_2") (pintype "passive"))
      (node (ref "R201") (pin "2") (pinfunction "2_2") (pintype "passive"))
      (node (ref "R35") (pin "1") (pinfunction "1_1") (pintype "passive"))
      (node (ref "U3") (pin "2") (pinfunction "EN_2") (pintype "input"))
    )
    (net (code "24") (name "Net-(U3-IN)") (class "Default")
      (node (ref "C13") (pin "1") (pinfunction "1_1") (pintype "passive"))
      (node (ref "R35") (pin "2") (pinfunction "2_2") (pintype "passive"))
      (node (ref "R41") (pin "2") (pinfunction "2_2") (pintype "passive"))
      (node (ref "U3") (pin "1") (pinfunction "IN_1") (pintype "input"))
    )
    (net (code "25") (name "Net-(U3-PG)") (class "Default")
      (node (ref "R43") (pin "1") (pinfunction "1_1") (pintype "passive"))
      (node (ref "U3") (pin "4") (pinfunction "PG_4") (pintype "open_collector"))
    )
    (net (code "26") (name "Net-(U3-SNS)") (class "Default")
      (node (ref "R44") (pin "1") (pinfunction "1_1") (pintype "passive"))
      (node (ref "R45") (pin "2") (pinfunction "2_2") (pintype "passive"))
      (node (ref "U3") (pin "5") (pinfunction "SNS_5") (pintype "input"))
    )
    (net (code "27") (name "VBUS") (class "Default")
      (node (ref "R29") (pin "1") (pinfunction "1_1") (pintype "passive"))
      (node (ref "R38") (pin "1") (pinfunction "1_1") (pintype "passive"))
      (node (ref "R41") (pin "1") (pinfunction "1_1") (pintype "passive"))
      (node (ref "SW1") (pin "1") (pinfunction "N.O-1_1") (pintype "passive"))
    )
    (net (code "28") (name "VDD") (class "Default")
      (node (ref "J3") (pin "2") (pinfunction "2_2") (pintype "passive"))
      (node (ref "R46") (pin "1") (pinfunction "1_1") (pintype "passive"))
    )
    (net (code "29") (name "VDDIO_Periph") (class "Default")
      (node (ref "R199") (pin "2") (pinfunction "2_2") (pintype "passive"))
    )
    (net (code "30") (name "VDD_M") (class "Default")
      (node (ref "J3") (pin "3") (pinfunction "3_3") (pintype "passive"))
      (node (ref "R199") (pin "1") (pinfunction "1_1") (pintype "passive"))
      (node (ref "R37") (pin "1") (pinfunction "1_1") (pintype "passive"))
      (node (ref "R46") (pin "2") (pinfunction "2_2") (pintype "passive"))
      (node (ref "SW2") (pin "2") (pinfunction "COM-1_2") (pintype "passive"))
    )
    (net (code "31") (name "V_Coin_Cell") (class "Default")
      (node (ref "C69") (pin "1") (pinfunction "1_1") (pintype "passive"))
      (node (ref "C70") (pin "1") (pinfunction "1_1") (pintype "passive"))
      (node (ref "D6") (pin "5") (pinfunction "OUT_5") (pintype "power_in"))
      (node (ref "D7") (pin "5") (pinfunction "OUT_5") (pintype "power_in"))
      (node (ref "R225") (pin "1") (pinfunction "1_1") (pintype "passive"))
      (node (ref "R37") (pin "2") (pinfunction "2_2") (pintype "passive"))
      (node (ref "SW2") (pin "1") (pinfunction "N.O-1_1") (pintype "passive"))
    )
    (net (code "32") (name "unconnected-(D4-IO3-Pad4)") (class "Default")
      (node (ref "D4") (pin "4") (pinfunction "IO3_4") (pintype "passive+no_connect"))
    )
    (net (code "33") (name "unconnected-(D5-NC-Pad4)") (class "Default")
      (node (ref "D5") (pin "4") (pinfunction "NC_4") (pintype "passive+no_connect"))
    )
    (net (code "34") (name "unconnected-(D6-NC-Pad4)") (class "Default")
      (node (ref "D6") (pin "4") (pinfunction "NC_4") (pintype "passive+no_connect"))
    )
    (net (code "35") (name "unconnected-(D7-NC-Pad4)") (class "Default")
      (node (ref "D7") (pin "4") (pinfunction "NC_4") (pintype "passive+no_connect"))
    )
    (net (code "36") (name "unconnected-(J2-SBU1-PadA8)") (class "Default")
      (node (ref "J2") (pin "A8") (pinfunction "SBU1_A8") (pintype "power_in+no_connect"))
    )
    (net (code "37") (name "unconnected-(J2-SBU2-PadB8)") (class "Default")
      (node (ref "J2") (pin "B8") (pinfunction "SBU2_B8") (pintype "power_in+no_connect"))
    )
    (net (code "38") (name "unconnected-(SW1-N.C-1-Pad3)") (class "Default")
      (node (ref "SW1") (pin "3") (pinfunction "N.C-1_3") (pintype "passive+no_connect"))
    )
    (net (code "39") (name "unconnected-(SW1-N.C-2-Pad6)") (class "Default")
      (node (ref "SW1") (pin "6") (pinfunction "N.C-2_6") (pintype "passive+no_connect"))
    )
    (net (code "40") (name "unconnected-(SW2-COM-2-Pad5)") (class "Default")
      (node (ref "SW2") (pin "5") (pinfunction "COM-2_5") (pintype "passive+no_connect"))
    )
    (net (code "41") (name "unconnected-(SW2-N.C-2-Pad6)") (class "Default")
      (node (ref "SW2") (pin "6") (pinfunction "N.C-2_6") (pintype "passive+no_connect"))
    )
    (net (code "42") (name "unconnected-(SW2-N.O-2-Pad4)") (class "Default")
      (node (ref "SW2") (pin "4") (pinfunction "N.O-2_4") (pintype "passive+no_connect"))
    )
  )
)
